# Control_Board1.net
KiCad netlist of a schematic drawn in EAGLE
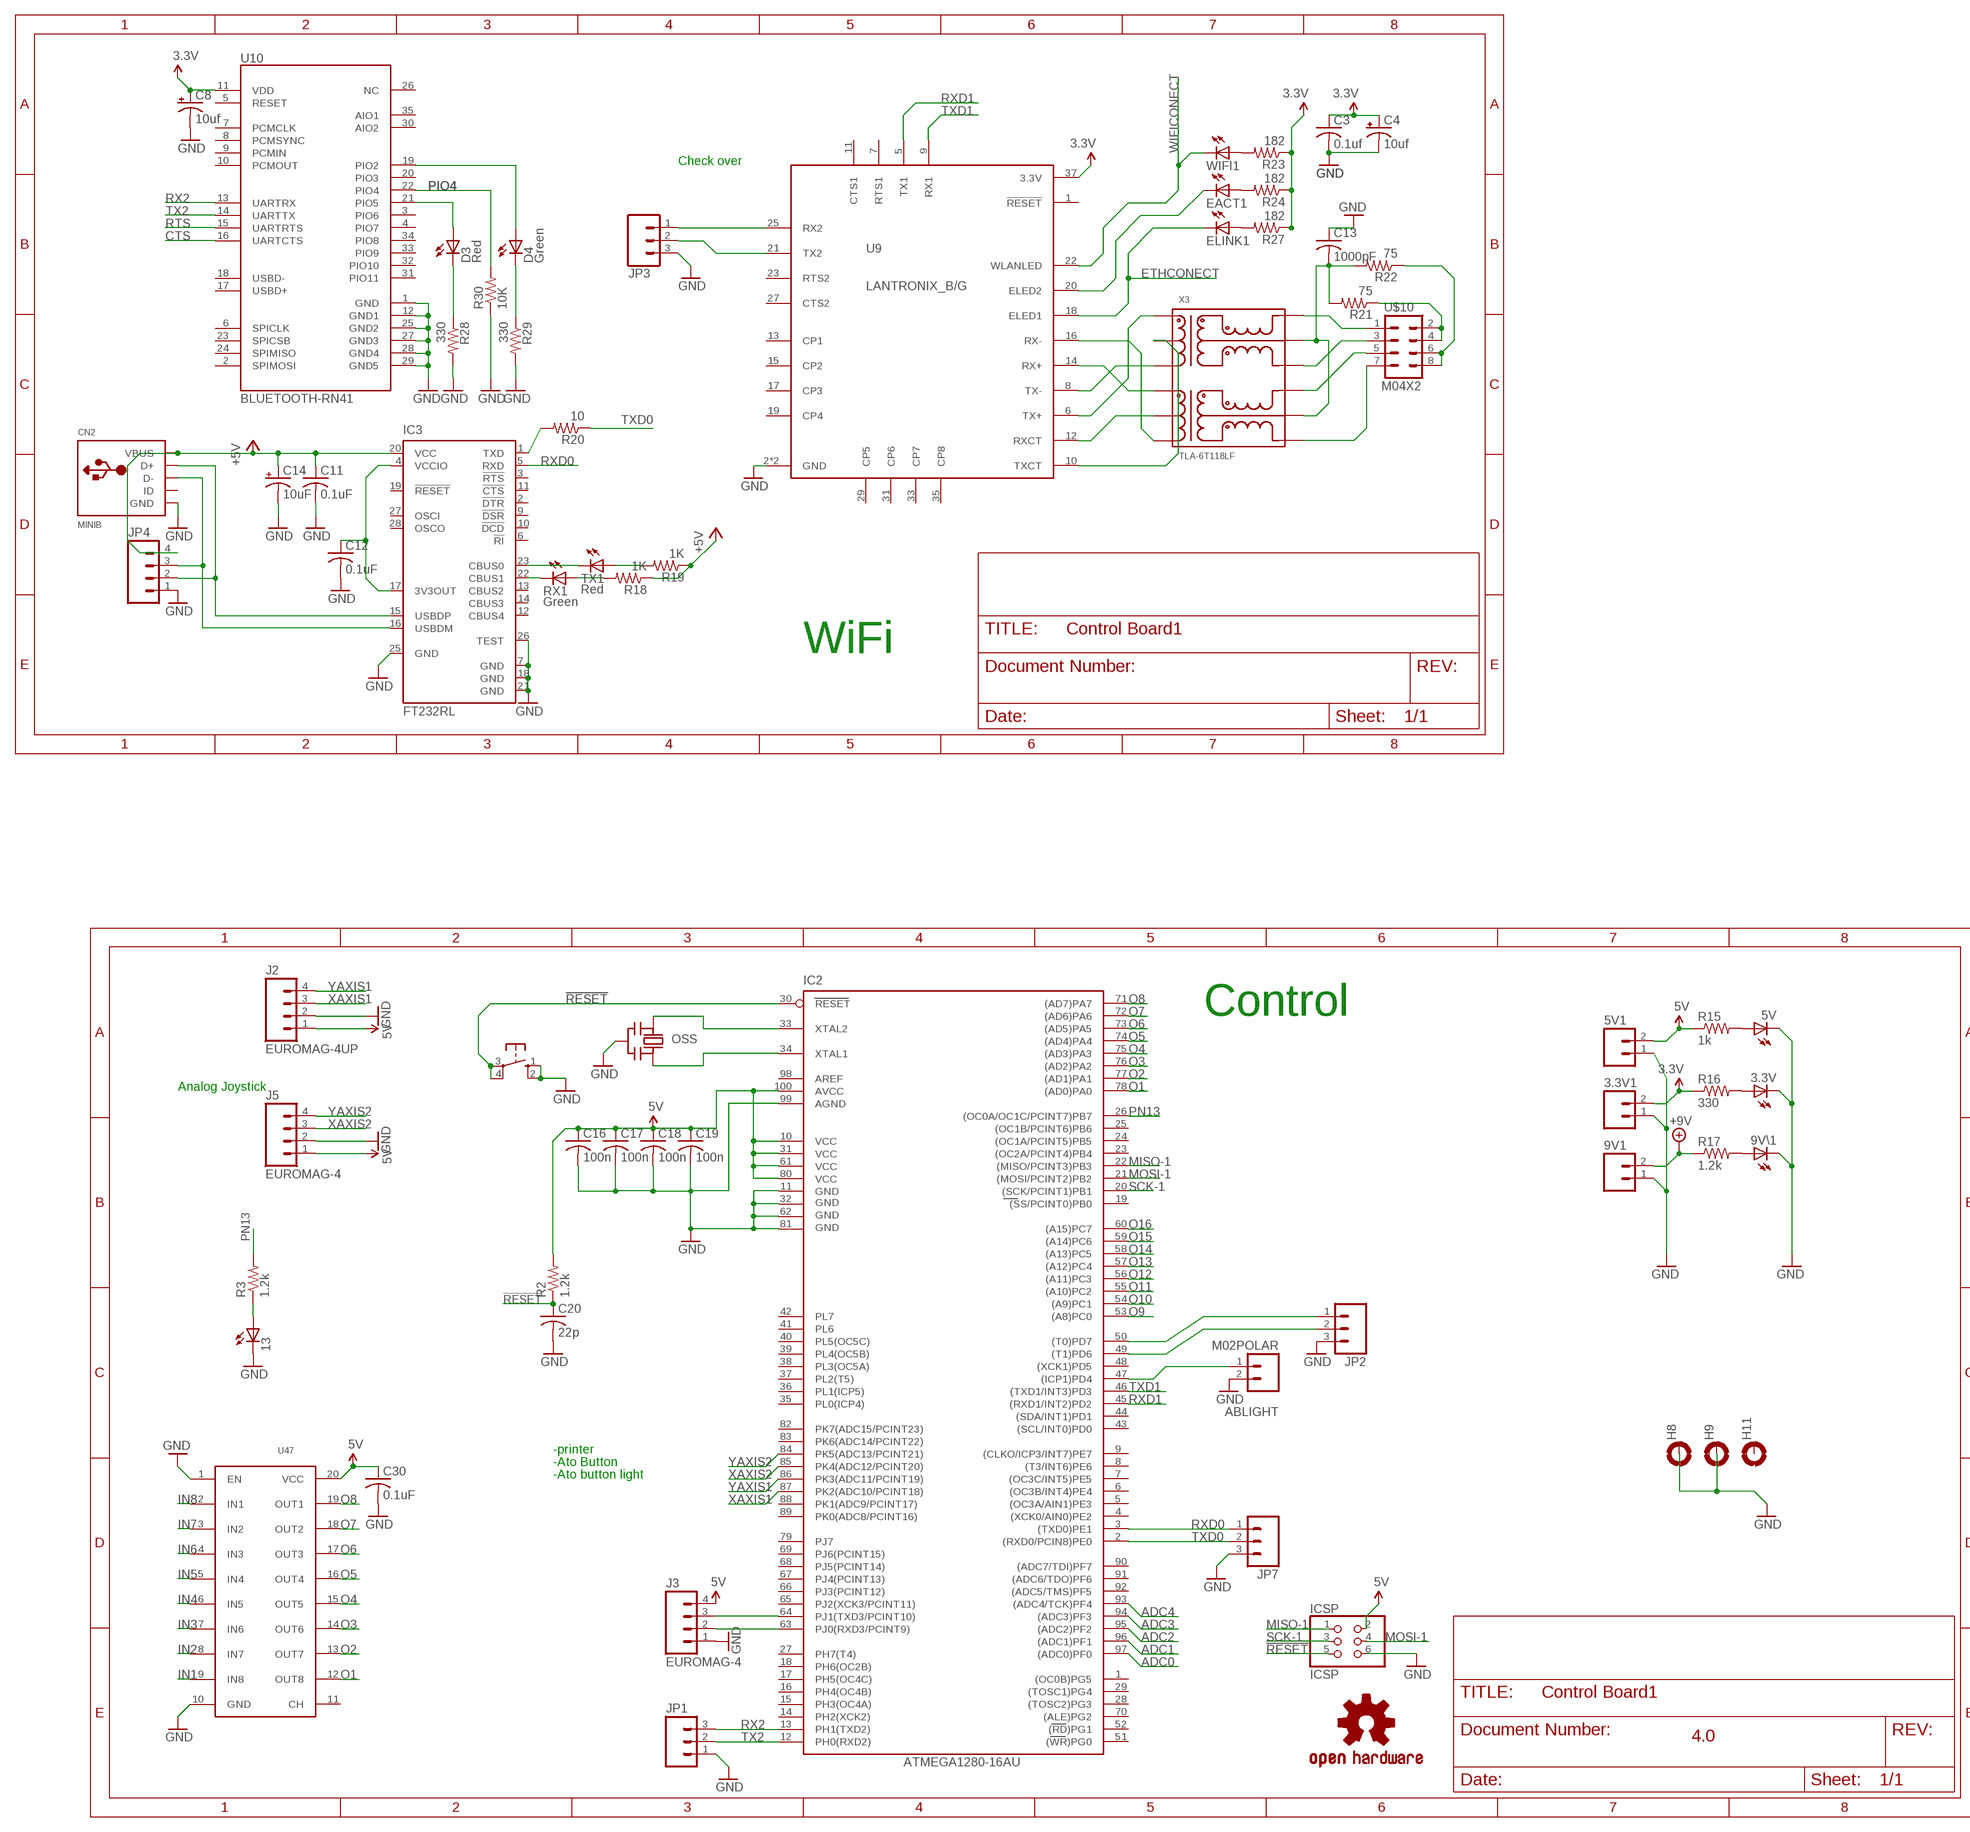
[diagram p0: schematic, sheet 1, part 1 of 2]
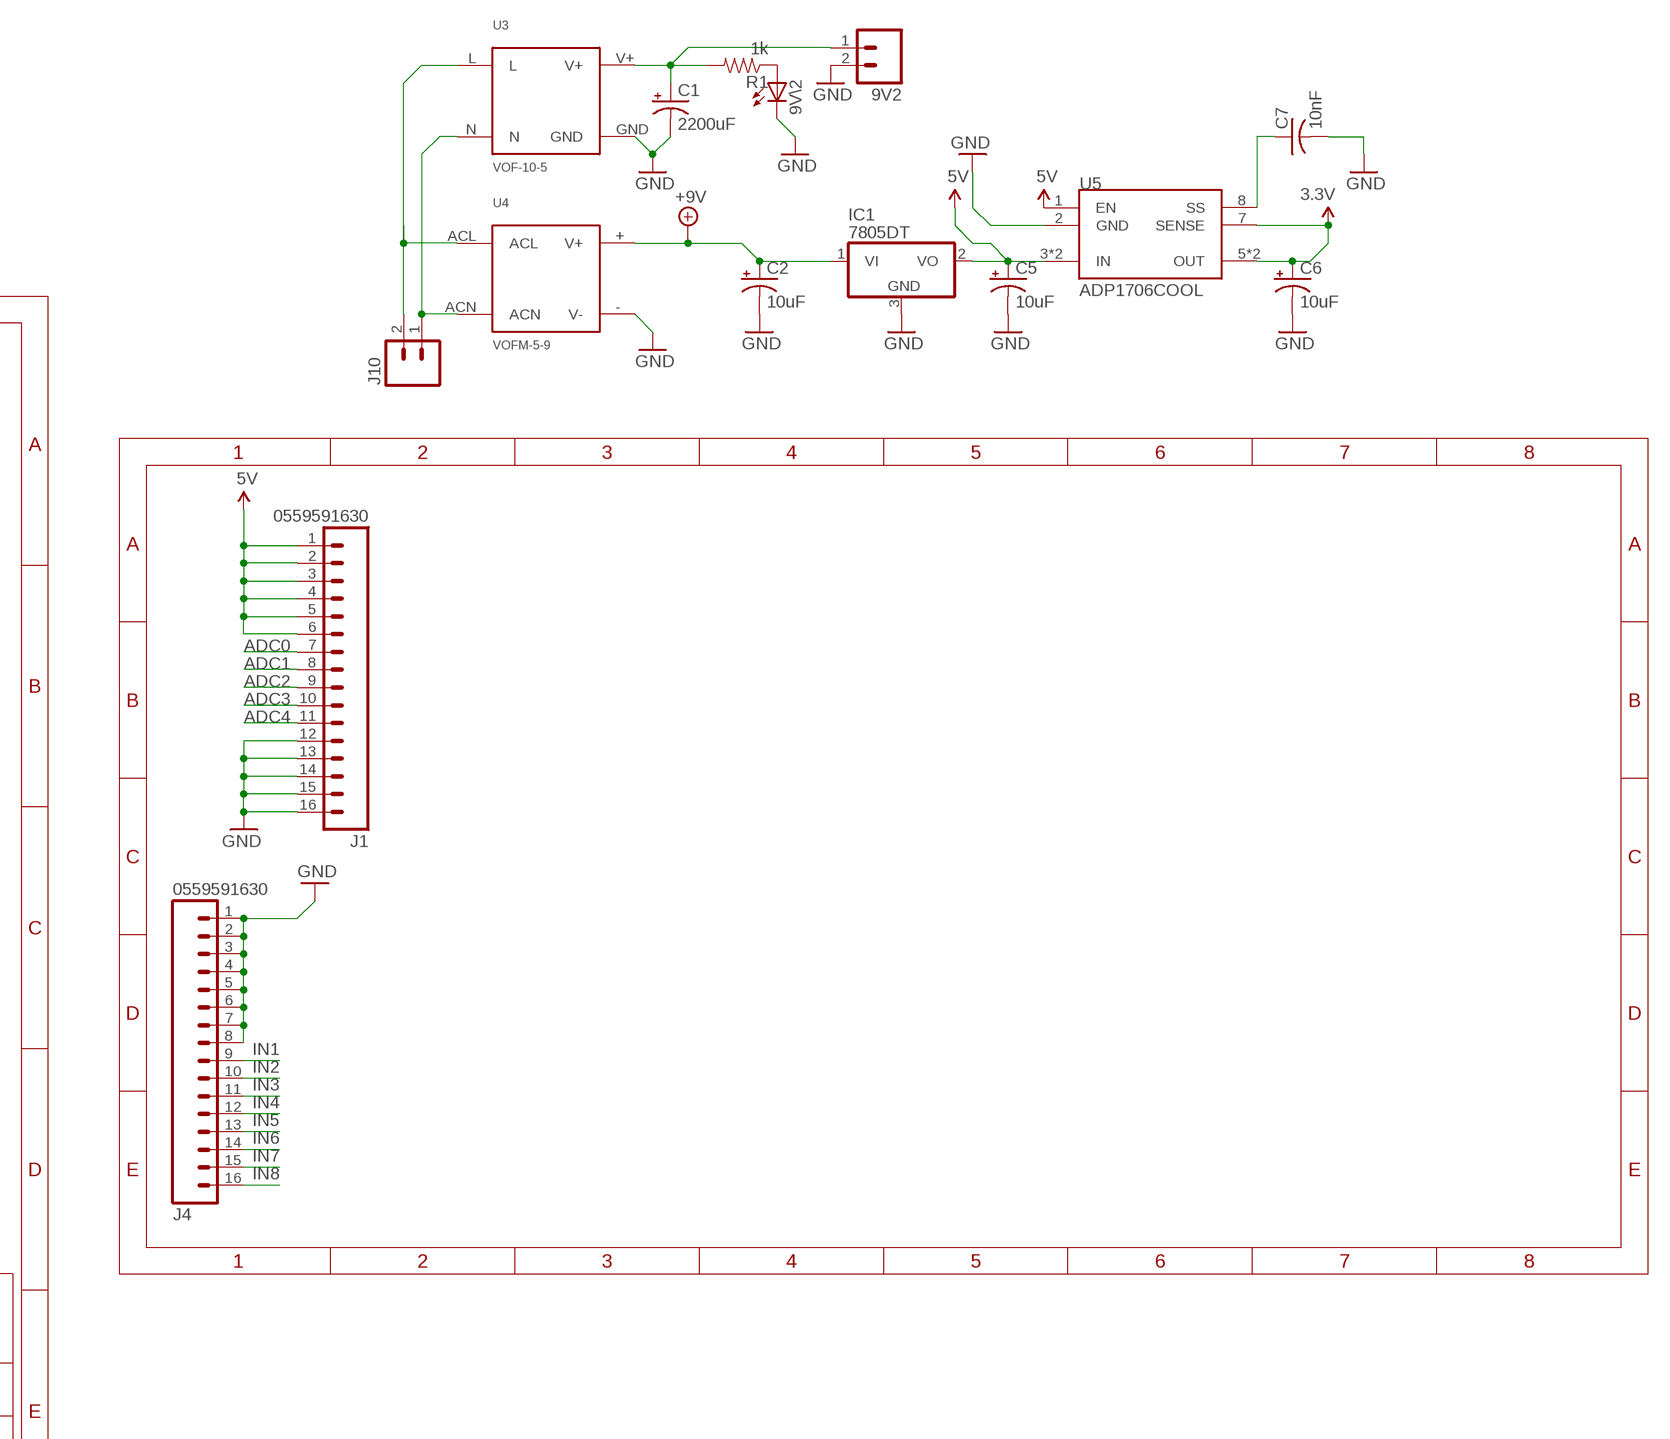
[diagram p1: schematic, sheet 1, part 2 of 2]

(export (version "E")
  (design (tool "Eeschema 10.0.6"))
  (components
    (comp (ref "3.3V")
      (value "LED-FKIT-1206")
      (footprint "eagle-import:FKIT-LED-1206")
      (libsource (lib "eagle-import") (part "LED-FKIT-1206"))
    )
    (comp (ref "3.3V1")
      (value "EUROMAG-290DEG")
      (footprint "eagle-import:M2")
      (libsource (lib "eagle-import") (part "EUROMAG-290DEG"))
    )
    (comp (ref "5V")
      (value "LED-FKIT-1206")
      (footprint "eagle-import:FKIT-LED-1206")
      (libsource (lib "eagle-import") (part "LED-FKIT-1206"))
    )
    (comp (ref "5V1")
      (value "EUROMAG-290DEG")
      (footprint "eagle-import:M2")
      (libsource (lib "eagle-import") (part "EUROMAG-290DEG"))
    )
    (comp (ref "9V1")
      (value "EUROMAG-290DEG")
      (footprint "eagle-import:M2")
      (libsource (lib "eagle-import") (part "EUROMAG-290DEG"))
    )
    (comp (ref "9V2")
      (value "EUROMAG-290DEG")
      (footprint "eagle-import:M2")
      (libsource (lib "eagle-import") (part "EUROMAG-290DEG"))
    )
    (comp (ref "9V\\1")
      (value "LED-FKIT-1206")
      (footprint "eagle-import:FKIT-LED-1206")
      (libsource (lib "eagle-import") (part "LED-FKIT-1206"))
    )
    (comp (ref "9V\\2")
      (value "LED-FKIT-1206")
      (footprint "eagle-import:FKIT-LED-1206")
      (libsource (lib "eagle-import") (part "LED-FKIT-1206"))
    )
    (comp (ref "13")
      (value "LEDCHIP-LED0805")
      (footprint "eagle-import:CHIP-LED0805")
      (libsource (lib "eagle-import") (part "LEDCHIP-LED0805"))
    )
    (comp (ref "ABLIGHT")
      (value "M02POLAR")
      (footprint "eagle-import:MOLEX-1X2")
      (libsource (lib "eagle-import") (part "M02POLAR"))
    )
    (comp (ref "C1")
      (value "2200uF")
      (footprint "eagle-import:EB20D")
      (libsource (lib "eagle-import") (part "CPOL-USE10-20"))
    )
    (comp (ref "C2")
      (value "10uF")
      (footprint "eagle-import:CT3528")
      (libsource (lib "eagle-import") (part "CPOL-USCT3528"))
    )
    (comp (ref "C3")
      (value "0.1uf")
      (footprint "eagle-import:C0805K")
      (libsource (lib "eagle-import") (part "C-USC0805K"))
    )
    (comp (ref "C4")
      (value "10uf")
      (footprint "eagle-import:EIA3528")
      (libsource (lib "eagle-import") (part "CAP_POL3528"))
    )
    (comp (ref "C5")
      (value "10uF")
      (footprint "eagle-import:CT3528")
      (libsource (lib "eagle-import") (part "CPOL-USCT3528"))
    )
    (comp (ref "C6")
      (value "10uF")
      (footprint "eagle-import:CT3528")
      (libsource (lib "eagle-import") (part "CPOL-USCT3528"))
    )
    (comp (ref "C7")
      (value "10nF")
      (footprint "eagle-import:C0805")
      (libsource (lib "eagle-import") (part "C-USC0805"))
    )
    (comp (ref "C8")
      (value "10uf")
      (footprint "eagle-import:EIA3528")
      (libsource (lib "eagle-import") (part "CAP_POL3528"))
    )
    (comp (ref "C11")
      (value "0.1uF")
      (footprint "eagle-import:C0805K")
      (libsource (lib "eagle-import") (part "C-USC0805K"))
    )
    (comp (ref "C12")
      (value "0.1uF")
      (footprint "eagle-import:C0805K")
      (libsource (lib "eagle-import") (part "C-USC0805K"))
    )
    (comp (ref "C13")
      (value "1000pF")
      (footprint "eagle-import:C1812")
      (libsource (lib "eagle-import") (part "C-USC1812"))
    )
    (comp (ref "C14")
      (value "10uF")
      (footprint "eagle-import:EIA3528-KIT")
      (libsource (lib "eagle-import") (part "CAP_POL3528-KIT"))
    )
    (comp (ref "C16")
      (value "100n")
      (footprint "eagle-import:C0805")
      (libsource (lib "eagle-import") (part "C-USC0805"))
    )
    (comp (ref "C17")
      (value "100n")
      (footprint "eagle-import:C0805")
      (libsource (lib "eagle-import") (part "C-USC0805"))
    )
    (comp (ref "C18")
      (value "100n")
      (footprint "eagle-import:C0805")
      (libsource (lib "eagle-import") (part "C-USC0805"))
    )
    (comp (ref "C19")
      (value "100n")
      (footprint "eagle-import:C0805")
      (libsource (lib "eagle-import") (part "C-USC0805"))
    )
    (comp (ref "C20")
      (value "22p")
      (footprint "eagle-import:C0805")
      (libsource (lib "eagle-import") (part "C-USC0805"))
    )
    (comp (ref "C30")
      (value "0.1uF")
      (footprint "eagle-import:C0805")
      (libsource (lib "eagle-import") (part "C-USC0805"))
    )
    (comp (ref "CN2")
      (value "MINIB")
      (footprint "eagle-import:USB-MINIB")
      (libsource (lib "eagle-import") (part "USBMINIB"))
    )
    (comp (ref "D3")
      (value "Red")
      (footprint "eagle-import:CHIP-LED0805")
      (libsource (lib "eagle-import") (part "LEDCHIP-LED0805"))
    )
    (comp (ref "D4")
      (value "Green")
      (footprint "eagle-import:CHIP-LED0805")
      (libsource (lib "eagle-import") (part "LEDCHIP-LED0805"))
    )
    (comp (ref "EACT1")
      (value "LEDCHIP-LED0805")
      (footprint "eagle-import:CHIP-LED0805")
      (libsource (lib "eagle-import") (part "LEDCHIP-LED0805"))
    )
    (comp (ref "ELINK1")
      (value "LEDCHIP-LED0805")
      (footprint "eagle-import:CHIP-LED0805")
      (libsource (lib "eagle-import") (part "LEDCHIP-LED0805"))
    )
    (comp (ref "H8")
      (value "MOUNT-PAD-ROUND2.8")
      (footprint "eagle-import:2,8-PAD")
      (libsource (lib "eagle-import") (part "MOUNT-PAD-ROUND2.8"))
    )
    (comp (ref "H9")
      (value "MOUNT-PAD-ROUND2.8")
      (footprint "eagle-import:2,8-PAD")
      (libsource (lib "eagle-import") (part "MOUNT-PAD-ROUND2.8"))
    )
    (comp (ref "H11")
      (value "MOUNT-PAD-ROUND2.8")
      (footprint "eagle-import:2,8-PAD")
      (libsource (lib "eagle-import") (part "MOUNT-PAD-ROUND2.8"))
    )
    (comp (ref "IC1")
      (value "7805DT")
      (footprint "eagle-import:TO252")
      (libsource (lib "eagle-import") (part "78DT05"))
    )
    (comp (ref "IC2")
      (value "ATMEGA1280-16AU")
      (footprint "eagle-import:TQFP100")
      (libsource (lib "eagle-import") (part "ATMEGAAU1280-16"))
    )
    (comp (ref "IC3")
      (value "FT232RL")
      (footprint "eagle-import:SSOP28")
      (libsource (lib "eagle-import") (part "FT232RL"))
    )
    (comp (ref "ICSP")
      (value "ICSP")
      (footprint "eagle-import:2X03")
      (libsource (lib "eagle-import") (part "PINHD-2X3"))
    )
    (comp (ref "J1")
      (value "0559591630")
      (footprint "eagle-import:0559591630")
      (libsource (lib "eagle-import") (part "0559591630"))
    )
    (comp (ref "J2")
      (value "EUROMAG-4UP")
      (footprint "eagle-import:M4-90")
      (libsource (lib "eagle-import") (part "EUROMAG-4UP"))
    )
    (comp (ref "J3")
      (value "EUROMAG-4")
      (footprint "eagle-import:M4")
      (libsource (lib "eagle-import") (part "EUROMAG-4"))
    )
    (comp (ref "J4")
      (value "0559591630")
      (footprint "eagle-import:0559591630")
      (libsource (lib "eagle-import") (part "0559591630"))
    )
    (comp (ref "J5")
      (value "EUROMAG-4")
      (footprint "eagle-import:M4")
      (libsource (lib "eagle-import") (part "EUROMAG-4"))
    )
    (comp (ref "J10")
      (value "EUROMAG-290DEG")
      (footprint "eagle-import:M2")
      (libsource (lib "eagle-import") (part "EUROMAG-290DEG"))
    )
    (comp (ref "JP1")
      (value "M03POLAR")
      (footprint "eagle-import:MOLEX-1X3")
      (libsource (lib "eagle-import") (part "M03POLAR"))
    )
    (comp (ref "JP2")
      (value "M03POLAR")
      (footprint "eagle-import:MOLEX-1X3")
      (libsource (lib "eagle-import") (part "M03POLAR"))
    )
    (comp (ref "JP3")
      (value "M03POLAR")
      (footprint "eagle-import:MOLEX-1X3")
      (libsource (lib "eagle-import") (part "M03POLAR"))
    )
    (comp (ref "JP4")
      (value "M04LOCK")
      (footprint "eagle-import:1X04_LOCK")
      (libsource (lib "eagle-import") (part "M04LOCK"))
    )
    (comp (ref "JP7")
      (value "M03LOCK")
      (footprint "eagle-import:1X03_LOCK")
      (libsource (lib "eagle-import") (part "M03LOCK"))
    )
    (comp (ref "OSS")
      (value "CERMOSCILL-AWCSR")
      (footprint "eagle-import:AWCSR")
      (libsource (lib "eagle-import") (part "CERMOSCILL-AWCSR"))
    )
    (comp (ref "R1")
      (value "1k")
      (footprint "eagle-import:0805")
      (libsource (lib "eagle-import") (part "RESISTOR0805-RES"))
    )
    (comp (ref "R2")
      (value "1.2k")
      (footprint "eagle-import:0805")
      (libsource (lib "eagle-import") (part "RESISTOR0805-RES"))
    )
    (comp (ref "R3")
      (value "1.2k")
      (footprint "eagle-import:0805")
      (libsource (lib "eagle-import") (part "RESISTOR0805-RES"))
    )
    (comp (ref "R15")
      (value "1k")
      (footprint "eagle-import:0805")
      (libsource (lib "eagle-import") (part "RESISTOR0805-RES"))
    )
    (comp (ref "R16")
      (value "330")
      (footprint "eagle-import:0805")
      (libsource (lib "eagle-import") (part "RESISTOR0805-RES"))
    )
    (comp (ref "R17")
      (value "1.2k")
      (footprint "eagle-import:0805")
      (libsource (lib "eagle-import") (part "RESISTOR0805-RES"))
    )
    (comp (ref "R18")
      (value "1K")
      (footprint "eagle-import:R0805@1")
      (libsource (lib "eagle-import") (part "R-US_R0805"))
    )
    (comp (ref "R19")
      (value "1K")
      (footprint "eagle-import:R0805@1")
      (libsource (lib "eagle-import") (part "R-US_R0805"))
    )
    (comp (ref "R20")
      (value "10")
      (footprint "eagle-import:R0805@1")
      (libsource (lib "eagle-import") (part "R-US_R0805"))
    )
    (comp (ref "R21")
      (value "75")
      (footprint "eagle-import:R0805@1")
      (libsource (lib "eagle-import") (part "R-US_R0805"))
    )
    (comp (ref "R22")
      (value "75")
      (footprint "eagle-import:R0805@1")
      (libsource (lib "eagle-import") (part "R-US_R0805"))
    )
    (comp (ref "R23")
      (value "182")
      (footprint "eagle-import:R0805@1")
      (libsource (lib "eagle-import") (part "R-US_R0805"))
    )
    (comp (ref "R24")
      (value "182")
      (footprint "eagle-import:R0805@1")
      (libsource (lib "eagle-import") (part "R-US_R0805"))
    )
    (comp (ref "R27")
      (value "182")
      (footprint "eagle-import:R0805@1")
      (libsource (lib "eagle-import") (part "R-US_R0805"))
    )
    (comp (ref "R28")
      (value "330")
      (footprint "eagle-import:0805")
      (libsource (lib "eagle-import") (part "RESISTOR0805-RES"))
    )
    (comp (ref "R29")
      (value "330")
      (footprint "eagle-import:0805")
      (libsource (lib "eagle-import") (part "RESISTOR0805-RES"))
    )
    (comp (ref "R30")
      (value "10K")
      (footprint "eagle-import:0805")
      (libsource (lib "eagle-import") (part "RESISTOR0805-RES"))
    )
    (comp (ref "RX1")
      (value "Green")
      (footprint "eagle-import:CHIP-LED0805")
      (libsource (lib "eagle-import") (part "LEDCHIP-LED0805"))
    )
    (comp (ref "S1")
      (value "10-XX")
      (footprint "eagle-import:B3F-10XX")
      (libsource (lib "eagle-import") (part "10-XX"))
    )
    (comp (ref "TX1")
      (value "Red")
      (footprint "eagle-import:CHIP-LED0805")
      (libsource (lib "eagle-import") (part "LEDCHIP-LED0805"))
    )
    (comp (ref "U$3")
      (value "OSHW-LOGOL")
      (footprint "eagle-import:OSHW-LOGO-L")
      (libsource (lib "eagle-import") (part "OSHW-LOGOL"))
    )
    (comp (ref "U$10")
      (value "M04X2")
      (footprint "eagle-import:2X4")
      (libsource (lib "eagle-import") (part "M04X2"))
    )
    (comp (ref "U3")
      (value "VOF-10-5")
      (footprint "eagle-import:VOF-10")
      (libsource (lib "eagle-import") (part "VOF-10"))
    )
    (comp (ref "U4")
      (value "VOFM-5-9")
      (footprint "eagle-import:VOFM-5")
      (libsource (lib "eagle-import") (part "VOFM-5"))
    )
    (comp (ref "U5")
      (value "ADP1706COOL")
      (footprint "eagle-import:SO-8COOL")
      (libsource (lib "eagle-import") (part "ADP1706COOL"))
    )
    (comp (ref "U9")
      (value "LANTRONIX_B/G")
      (footprint "eagle-import:LANA_BTH")
      (libsource (lib "eagle-import") (part "LANTRONIX_A/B"))
    )
    (comp (ref "U10")
      (value "BLUETOOTH-RN41")
      (footprint "eagle-import:RN41")
      (libsource (lib "eagle-import") (part "BLUETOOTH-RN41{dblquote}"))
    )
    (comp (ref "U47")
      (value "MAX6818")
      (footprint "eagle-import:SSOP-20")
      (libsource (lib "eagle-import") (part "MAX6818"))
    )
    (comp (ref "WIFI1")
      (value "LEDCHIP-LED0805")
      (footprint "eagle-import:CHIP-LED0805")
      (libsource (lib "eagle-import") (part "LEDCHIP-LED0805"))
    )
    (comp (ref "X3")
      (value "TLA-6T118LF")
      (footprint "eagle-import:SO-16MOD")
      (libsource (lib "eagle-import") (part "TLA-6T118LF"))
    )
  )
  (nets
    (net (code "1") (name "+5V") (class "Default")
      (node (ref "C11") (pin "1") (pinfunction "1_1") (pintype "passive"))
      (node (ref "C14") (pin "A") (pinfunction "+_A") (pintype "passive"))
      (node (ref "CN2") (pin "VBUS") (pinfunction "VBUS_VBUS") (pintype "power_in"))
      (node (ref "IC3") (pin "20") (pinfunction "VCC_20") (pintype "input"))
      (node (ref "JP4") (pin "4") (pinfunction "4_4") (pintype "passive"))
      (node (ref "R18") (pin "1") (pinfunction "1_1") (pintype "passive"))
      (node (ref "R19") (pin "1") (pinfunction "1_1") (pintype "passive"))
    )
    (net (code "2") (name "+9V") (class "Default")
      (node (ref "9V1") (pin "2") (pinfunction "2_2") (pintype "passive"))
      (node (ref "C2") (pin "+") (pinfunction "+_+") (pintype "passive"))
      (node (ref "IC1") (pin "1") (pinfunction "VI_1") (pintype "input"))
      (node (ref "R17") (pin "1") (pinfunction "1_1") (pintype "passive"))
      (node (ref "U4") (pin "+") (pinfunction "V+_+") (pintype "bidirectional"))
    )
    (net (code "3") (name "/ADC0") (class "Default")
      (node (ref "IC2") (pin "97") (pinfunction "(ADC0)PF0_97") (pintype "bidirectional"))
      (node (ref "J1") (pin "7") (pinfunction "7_7") (pintype "passive"))
    )
    (net (code "4") (name "/ADC1") (class "Default")
      (node (ref "IC2") (pin "96") (pinfunction "(ADC1)PF1_96") (pintype "bidirectional"))
      (node (ref "J1") (pin "8") (pinfunction "8_8") (pintype "passive"))
    )
    (net (code "5") (name "/ADC2") (class "Default")
      (node (ref "IC2") (pin "95") (pinfunction "(ADC2)PF2_95") (pintype "bidirectional"))
      (node (ref "J1") (pin "9") (pinfunction "9_9") (pintype "passive"))
    )
    (net (code "6") (name "/ADC3") (class "Default")
      (node (ref "IC2") (pin "94") (pinfunction "(ADC3)PF3_94") (pintype "bidirectional"))
      (node (ref "J1") (pin "10") (pinfunction "10_10") (pintype "passive"))
    )
    (net (code "7") (name "/ADC4") (class "Default")
      (node (ref "IC2") (pin "93") (pinfunction "(ADC4/TCK)PF4_93") (pintype "bidirectional"))
      (node (ref "J1") (pin "11") (pinfunction "11_11") (pintype "passive"))
    )
    (net (code "8") (name "/CTS") (class "Default")
      (node (ref "U10") (pin "16") (pinfunction "UARTCTS_16") (pintype "bidirectional"))
    )
    (net (code "9") (name "/ETHCONECT") (class "Default")
      (node (ref "ELINK1") (pin "C") (pinfunction "C_C") (pintype "passive"))
      (node (ref "U9") (pin "18") (pinfunction "ELED1_18") (pintype "bidirectional"))
    )
    (net (code "10") (name "/IN1") (class "Default")
      (node (ref "J4") (pin "9") (pinfunction "9_9") (pintype "passive"))
      (node (ref "U47") (pin "9") (pinfunction "IN8_9") (pintype "bidirectional"))
    )
    (net (code "11") (name "/IN2") (class "Default")
      (node (ref "J4") (pin "10") (pinfunction "10_10") (pintype "passive"))
      (node (ref "U47") (pin "8") (pinfunction "IN7_8") (pintype "bidirectional"))
    )
    (net (code "12") (name "/IN3") (class "Default")
      (node (ref "J4") (pin "11") (pinfunction "11_11") (pintype "passive"))
      (node (ref "U47") (pin "7") (pinfunction "IN6_7") (pintype "bidirectional"))
    )
    (net (code "13") (name "/IN4") (class "Default")
      (node (ref "J4") (pin "12") (pinfunction "12_12") (pintype "passive"))
      (node (ref "U47") (pin "6") (pinfunction "IN5_6") (pintype "bidirectional"))
    )
    (net (code "14") (name "/IN5") (class "Default")
      (node (ref "J4") (pin "13") (pinfunction "13_13") (pintype "passive"))
      (node (ref "U47") (pin "5") (pinfunction "IN4_5") (pintype "bidirectional"))
    )
    (net (code "15") (name "/IN6") (class "Default")
      (node (ref "J4") (pin "14") (pinfunction "14_14") (pintype "passive"))
      (node (ref "U47") (pin "4") (pinfunction "IN3_4") (pintype "bidirectional"))
    )
    (net (code "16") (name "/IN7") (class "Default")
      (node (ref "J4") (pin "15") (pinfunction "15_15") (pintype "passive"))
      (node (ref "U47") (pin "3") (pinfunction "IN2_3") (pintype "bidirectional"))
    )
    (net (code "17") (name "/IN8") (class "Default")
      (node (ref "J4") (pin "16") (pinfunction "16_16") (pintype "passive"))
      (node (ref "U47") (pin "2") (pinfunction "IN1_2") (pintype "bidirectional"))
    )
    (net (code "18") (name "/MISO-1") (class "Default")
      (node (ref "IC2") (pin "22") (pinfunction "(MISO/PCINT3)PB3_22") (pintype "bidirectional"))
      (node (ref "ICSP") (pin "1") (pinfunction "1_1") (pintype "passive"))
    )
    (net (code "19") (name "/MOSI-1") (class "Default")
      (node (ref "IC2") (pin "21") (pinfunction "(MOSI/PCINT2)PB2_21") (pintype "bidirectional"))
      (node (ref "ICSP") (pin "4") (pinfunction "4_4") (pintype "passive"))
    )
    (net (code "20") (name "/O1") (class "Default")
      (node (ref "IC2") (pin "78") (pinfunction "(AD0)PA0_78") (pintype "bidirectional"))
      (node (ref "U47") (pin "12") (pinfunction "OUT8_12") (pintype "bidirectional"))
    )
    (net (code "21") (name "/O2") (class "Default")
      (node (ref "IC2") (pin "77") (pinfunction "(AD1)PA1_77") (pintype "bidirectional"))
      (node (ref "U47") (pin "13") (pinfunction "OUT7_13") (pintype "bidirectional"))
    )
    (net (code "22") (name "/O3") (class "Default")
      (node (ref "IC2") (pin "76") (pinfunction "(AD2)PA2_76") (pintype "bidirectional"))
      (node (ref "U47") (pin "14") (pinfunction "OUT6_14") (pintype "bidirectional"))
    )
    (net (code "23") (name "/O4") (class "Default")
      (node (ref "IC2") (pin "75") (pinfunction "(AD3)PA3_75") (pintype "bidirectional"))
      (node (ref "U47") (pin "15") (pinfunction "OUT5_15") (pintype "bidirectional"))
    )
    (net (code "24") (name "/O5") (class "Default")
      (node (ref "IC2") (pin "74") (pinfunction "(AD4)PA4_74") (pintype "bidirectional"))
      (node (ref "U47") (pin "16") (pinfunction "OUT4_16") (pintype "bidirectional"))
    )
    (net (code "25") (name "/O6") (class "Default")
      (node (ref "IC2") (pin "73") (pinfunction "(AD5)PA5_73") (pintype "bidirectional"))
      (node (ref "U47") (pin "17") (pinfunction "OUT3_17") (pintype "bidirectional"))
    )
    (net (code "26") (name "/O7") (class "Default")
      (node (ref "IC2") (pin "72") (pinfunction "(AD6)PA6_72") (pintype "bidirectional"))
      (node (ref "U47") (pin "18") (pinfunction "OUT2_18") (pintype "bidirectional"))
    )
    (net (code "27") (name "/O8") (class "Default")
      (node (ref "IC2") (pin "71") (pinfunction "(AD7)PA7_71") (pintype "bidirectional"))
      (node (ref "U47") (pin "19") (pinfunction "OUT1_19") (pintype "bidirectional"))
    )
    (net (code "28") (name "/O9") (class "Default")
      (node (ref "IC2") (pin "53") (pinfunction "(A8)PC0_53") (pintype "bidirectional"))
    )
    (net (code "29") (name "/O10") (class "Default")
      (node (ref "IC2") (pin "54") (pinfunction "(A9)PC1_54") (pintype "bidirectional"))
    )
    (net (code "30") (name "/O11") (class "Default")
      (node (ref "IC2") (pin "55") (pinfunction "(A10)PC2_55") (pintype "bidirectional"))
    )
    (net (code "31") (name "/O12") (class "Default")
      (node (ref "IC2") (pin "56") (pinfunction "(A11)PC3_56") (pintype "bidirectional"))
    )
    (net (code "32") (name "/O13") (class "Default")
      (node (ref "IC2") (pin "57") (pinfunction "(A12)PC4_57") (pintype "bidirectional"))
    )
    (net (code "33") (name "/O14") (class "Default")
      (node (ref "IC2") (pin "58") (pinfunction "(A13)PC5_58") (pintype "bidirectional"))
    )
    (net (code "34") (name "/O15") (class "Default")
      (node (ref "IC2") (pin "59") (pinfunction "(A14)PC6_59") (pintype "bidirectional"))
    )
    (net (code "35") (name "/O16") (class "Default")
      (node (ref "IC2") (pin "60") (pinfunction "(A15)PC7_60") (pintype "bidirectional"))
    )
    (net (code "36") (name "/PIO4") (class "Default")
      (node (ref "R30") (pin "2") (pinfunction "2_2") (pintype "passive"))
      (node (ref "U10") (pin "22") (pinfunction "PIO4_22") (pintype "bidirectional"))
    )
    (net (code "37") (name "/PN13") (class "Default")
      (node (ref "IC2") (pin "26") (pinfunction "(OC0A/OC1C/PCINT7)PB7_26") (pintype "bidirectional"))
      (node (ref "R3") (pin "2") (pinfunction "2_2") (pintype "passive"))
    )
    (net (code "38") (name "/RTS") (class "Default")
      (node (ref "U10") (pin "15") (pinfunction "UARTRTS_15") (pintype "bidirectional"))
    )
    (net (code "39") (name "/RX2") (class "Default")
      (node (ref "IC2") (pin "13") (pinfunction "PH1(TXD2)_13") (pintype "bidirectional"))
      (node (ref "JP1") (pin "3") (pinfunction "3_3") (pintype "passive"))
      (node (ref "U10") (pin "13") (pinfunction "UARTRX_13") (pintype "bidirectional"))
    )
    (net (code "40") (name "/RXD0") (class "Default")
      (node (ref "IC2") (pin "3") (pinfunction "(TXD0)PE1_3") (pintype "bidirectional"))
      (node (ref "IC3") (pin "5") (pinfunction "RXD_5") (pintype "input"))
      (node (ref "JP7") (pin "1") (pinfunction "1_1") (pintype "passive"))
    )
    (net (code "41") (name "/RXD1") (class "Default")
      (node (ref "IC2") (pin "45") (pinfunction "(RXD1/INT2)PD2_45") (pintype "bidirectional"))
      (node (ref "U9") (pin "5") (pinfunction "TX1_5") (pintype "bidirectional"))
    )
    (net (code "42") (name "/SCK-1") (class "Default")
      (node (ref "IC2") (pin "20") (pinfunction "(SCK/PCINT1)PB1_20") (pintype "bidirectional"))
      (node (ref "ICSP") (pin "3") (pinfunction "3_3") (pintype "passive"))
    )
    (net (code "43") (name "/TX2") (class "Default")
      (node (ref "IC2") (pin "12") (pinfunction "PH0(RXD2)_12") (pintype "bidirectional"))
      (node (ref "JP1") (pin "2") (pinfunction "2_2") (pintype "passive"))
      (node (ref "U10") (pin "14") (pinfunction "UARTTX_14") (pintype "bidirectional"))
    )
    (net (code "44") (name "/TXD0") (class "Default")
      (node (ref "IC2") (pin "2") (pinfunction "(RXD0/PCIN8)PE0_2") (pintype "bidirectional"))
      (node (ref "JP7") (pin "2") (pinfunction "2_2") (pintype "passive"))
      (node (ref "R20") (pin "1") (pinfunction "1_1") (pintype "passive"))
    )
    (net (code "45") (name "/TXD1") (class "Default")
      (node (ref "IC2") (pin "46") (pinfunction "(TXD1/INT3)PD3_46") (pintype "bidirectional"))
      (node (ref "U9") (pin "9") (pinfunction "RX1_9") (pintype "bidirectional"))
    )
    (net (code "46") (name "/WIFICONECT") (class "Default")
      (node (ref "U9") (pin "22") (pinfunction "WLANLED_22") (pintype "bidirectional"))
      (node (ref "WIFI1") (pin "C") (pinfunction "C_C") (pintype "passive"))
    )
    (net (code "47") (name "/XAXIS1") (class "Default")
      (node (ref "IC2") (pin "87") (pinfunction "PK2(ADC10/PCINT18)_87") (pintype "bidirectional"))
      (node (ref "J2") (pin "3") (pinfunction "3_3") (pintype "passive"))
    )
    (net (code "48") (name "/XAXIS2") (class "Default")
      (node (ref "IC2") (pin "85") (pinfunction "PK4(ADC12/PCINT20)_85") (pintype "bidirectional"))
      (node (ref "J5") (pin "3") (pinfunction "3_3") (pintype "passive"))
    )
    (net (code "49") (name "/YAXIS1") (class "Default")
      (node (ref "IC2") (pin "86") (pinfunction "PK3(ADC11/PCINT19)_86") (pintype "bidirectional"))
      (node (ref "J2") (pin "4") (pinfunction "4_4") (pintype "passive"))
    )
    (net (code "50") (name "/YAXIS2") (class "Default")
      (node (ref "IC2") (pin "84") (pinfunction "PK5(ADC13/PCINT21)_84") (pintype "bidirectional"))
      (node (ref "J5") (pin "4") (pinfunction "4_4") (pintype "passive"))
    )
    (net (code "51") (name "/~{RESET}") (class "Default")
      (node (ref "C20") (pin "1") (pinfunction "1_1") (pintype "passive"))
      (node (ref "IC2") (pin "30") (pinfunction "RESET_30") (pintype "input"))
      (node (ref "ICSP") (pin "5") (pinfunction "5_5") (pintype "passive"))
      (node (ref "R2") (pin "1") (pinfunction "1_1") (pintype "passive"))
      (node (ref "S1") (pin "3") (pinfunction "P_3") (pintype "passive"))
      (node (ref "S1") (pin "4") (pinfunction "P1_4") (pintype "passive"))
    )
    (net (code "52") (name "3.3V") (class "Default")
      (node (ref "3.3V1") (pin "2") (pinfunction "2_2") (pintype "passive"))
      (node (ref "C3") (pin "1") (pinfunction "1_1") (pintype "passive"))
      (node (ref "C4") (pin "A") (pinfunction "+_A") (pintype "passive"))
      (node (ref "C6") (pin "+") (pinfunction "+_+") (pintype "passive"))
      (node (ref "C8") (pin "A") (pinfunction "+_A") (pintype "passive"))
      (node (ref "R16") (pin "1") (pinfunction "1_1") (pintype "passive"))
      (node (ref "R23") (pin "1") (pinfunction "1_1") (pintype "passive"))
      (node (ref "R24") (pin "1") (pinfunction "1_1") (pintype "passive"))
      (node (ref "R27") (pin "1") (pinfunction "1_1") (pintype "passive"))
      (node (ref "U10") (pin "11") (pinfunction "VDD_11") (pintype "bidirectional"))
      (node (ref "U5") (pin "5") (pinfunction "OUT_5") (pintype "bidirectional"))
      (node (ref "U5") (pin "6") (pinfunction "OUT_6") (pintype "bidirectional"))
      (node (ref "U5") (pin "7") (pinfunction "SENSE_7") (pintype "bidirectional"))
      (node (ref "U9") (pin "37") (pinfunction "3.3V_37") (pintype "bidirectional"))
    )
    (net (code "53") (name "5V") (class "Default")
      (node (ref "5V1") (pin "2") (pinfunction "2_2") (pintype "passive"))
      (node (ref "C16") (pin "1") (pinfunction "1_1") (pintype "passive"))
      (node (ref "C17") (pin "1") (pinfunction "1_1") (pintype "passive"))
      (node (ref "C18") (pin "1") (pinfunction "1_1") (pintype "passive"))
      (node (ref "C19") (pin "1") (pinfunction "1_1") (pintype "passive"))
      (node (ref "C30") (pin "1") (pinfunction "1_1") (pintype "passive"))
      (node (ref "C5") (pin "+") (pinfunction "+_+") (pintype "passive"))
      (node (ref "IC1") (pin "2") (pinfunction "VO_2") (pintype "passive"))
      (node (ref "IC2") (pin "10") (pinfunction "VCC_10") (pintype "power_in"))
      (node (ref "IC2") (pin "100") (pinfunction "AVCC_100") (pintype "power_in"))
      (node (ref "IC2") (pin "31") (pinfunction "VCC1_31") (pintype "power_in"))
      (node (ref "IC2") (pin "61") (pinfunction "VCC2_61") (pintype "power_in"))
      (node (ref "IC2") (pin "80") (pinfunction "VCC3_80") (pintype "power_in"))
      (node (ref "ICSP") (pin "2") (pinfunction "2_2") (pintype "passive"))
      (node (ref "J1") (pin "1") (pinfunction "1_1") (pintype "passive"))
      (node (ref "J1") (pin "2") (pinfunction "2_2") (pintype "passive"))
      (node (ref "J1") (pin "3") (pinfunction "3_3") (pintype "passive"))
      (node (ref "J1") (pin "4") (pinfunction "4_4") (pintype "passive"))
      (node (ref "J1") (pin "5") (pinfunction "5_5") (pintype "passive"))
      (node (ref "J1") (pin "6") (pinfunction "6_6") (pintype "passive"))
      (node (ref "J2") (pin "1") (pinfunction "1_1") (pintype "passive"))
      (node (ref "J3") (pin "4") (pinfunction "4_4") (pintype "passive"))
      (node (ref "J5") (pin "1") (pinfunction "1_1") (pintype "passive"))
      (node (ref "R15") (pin "1") (pinfunction "1_1") (pintype "passive"))
      (node (ref "R2") (pin "2") (pinfunction "2_2") (pintype "passive"))
      (node (ref "U47") (pin "20") (pinfunction "VCC_20") (pintype "bidirectional"))
      (node (ref "U5") (pin "1") (pinfunction "EN_1") (pintype "bidirectional"))
      (node (ref "U5") (pin "3") (pinfunction "IN_3") (pintype "bidirectional"))
      (node (ref "U5") (pin "4") (pinfunction "IN_4") (pintype "bidirectional"))
    )
    (net (code "54") (name "GND") (class "Default")
      (node (ref "13") (pin "C") (pinfunction "C_C") (pintype "passive"))
      (node (ref "3.3V") (pin "C") (pinfunction "C_C") (pintype "passive"))
      (node (ref "3.3V1") (pin "1") (pinfunction "1_1") (pintype "passive"))
      (node (ref "5V") (pin "C") (pinfunction "C_C") (pintype "passive"))
      (node (ref "5V1") (pin "1") (pinfunction "1_1") (pintype "passive"))
      (node (ref "9V1") (pin "1") (pinfunction "1_1") (pintype "passive"))
      (node (ref "9V2") (pin "2") (pinfunction "2_2") (pintype "passive"))
      (node (ref "9V\\1") (pin "C") (pinfunction "C_C") (pintype "passive"))
      (node (ref "9V\\2") (pin "C") (pinfunction "C_C") (pintype "passive"))
      (node (ref "ABLIGHT") (pin "2") (pinfunction "2_2") (pintype "passive"))
      (node (ref "C1") (pin "-") (pinfunction "-_-") (pintype "passive"))
      (node (ref "C11") (pin "2") (pinfunction "2_2") (pintype "passive"))
      (node (ref "C12") (pin "2") (pinfunction "2_2") (pintype "passive"))
      (node (ref "C13") (pin "1") (pinfunction "1_1") (pintype "passive"))
      (node (ref "C14") (pin "C") (pinfunction "-_C") (pintype "passive"))
      (node (ref "C16") (pin "2") (pinfunction "2_2") (pintype "passive"))
      (node (ref "C17") (pin "2") (pinfunction "2_2") (pintype "passive"))
      (node (ref "C18") (pin "2") (pinfunction "2_2") (pintype "passive"))
      (node (ref "C19") (pin "2") (pinfunction "2_2") (pintype "passive"))
      (node (ref "C2") (pin "-") (pinfunction "-_-") (pintype "passive"))
      (node (ref "C20") (pin "2") (pinfunction "2_2") (pintype "passive"))
      (node (ref "C3") (pin "2") (pinfunction "2_2") (pintype "passive"))
      (node (ref "C30") (pin "2") (pinfunction "2_2") (pintype "passive"))
      (node (ref "C4") (pin "C") (pinfunction "-_C") (pintype "passive"))
      (node (ref "C5") (pin "-") (pinfunction "-_-") (pintype "passive"))
      (node (ref "C6") (pin "-") (pinfunction "-_-") (pintype "passive"))
      (node (ref "C7") (pin "2") (pinfunction "2_2") (pintype "passive"))
      (node (ref "C8") (pin "C") (pinfunction "-_C") (pintype "passive"))
      (node (ref "CN2") (pin "GND") (pinfunction "GND_GND") (pintype "power_in"))
      (node (ref "H8") (pin "B2,8") (pinfunction "MOUNT_B2,8") (pintype "passive"))
      (node (ref "H9") (pin "B2,8") (pinfunction "MOUNT_B2,8") (pintype "passive"))
      (node (ref "IC1") (pin "3") (pinfunction "GND_3") (pintype "passive"))
      (node (ref "IC2") (pin "11") (pinfunction "GND_11") (pintype "power_in"))
      (node (ref "IC2") (pin "32") (pinfunction "GND1_32") (pintype "power_in"))
      (node (ref "IC2") (pin "62") (pinfunction "GND2_62") (pintype "power_in"))
      (node (ref "IC2") (pin "81") (pinfunction "GND3_81") (pintype "power_in"))
      (node (ref "IC2") (pin "99") (pinfunction "AGND_99") (pintype "power_in"))
      (node (ref "IC3") (pin "18") (pinfunction "GND_18") (pintype "input"))
      (node (ref "IC3") (pin "21") (pinfunction "GND_21") (pintype "input"))
      (node (ref "IC3") (pin "25") (pinfunction "GND_25") (pintype "input"))
      (node (ref "IC3") (pin "26") (pinfunction "TEST_26") (pintype "input"))
      (node (ref "IC3") (pin "7") (pinfunction "GND_7") (pintype "input"))
      (node (ref "ICSP") (pin "6") (pinfunction "6_6") (pintype "passive"))
      (node (ref "J1") (pin "12") (pinfunction "12_12") (pintype "passive"))
      (node (ref "J1") (pin "13") (pinfunction "13_13") (pintype "passive"))
      (node (ref "J1") (pin "14") (pinfunction "14_14") (pintype "passive"))
      (node (ref "J1") (pin "15") (pinfunction "15_15") (pintype "passive"))
      (node (ref "J1") (pin "16") (pinfunction "16_16") (pintype "passive"))
      (node (ref "J2") (pin "2") (pinfunction "2_2") (pintype "passive"))
      (node (ref "J3") (pin "1") (pinfunction "1_1") (pintype "passive"))
      (node (ref "J4") (pin "1") (pinfunction "1_1") (pintype "passive"))
      (node (ref "J4") (pin "2") (pinfunction "2_2") (pintype "passive"))
      (node (ref "J4") (pin "3") (pinfunction "3_3") (pintype "passive"))
      (node (ref "J4") (pin "4") (pinfunction "4_4") (pintype "passive"))
      (node (ref "J4") (pin "5") (pinfunction "5_5") (pintype "passive"))
      (node (ref "J4") (pin "6") (pinfunction "6_6") (pintype "passive"))
      (node (ref "J4") (pin "7") (pinfunction "7_7") (pintype "passive"))
      (node (ref "J4") (pin "8") (pinfunction "8_8") (pintype "passive"))
      (node (ref "J5") (pin "2") (pinfunction "2_2") (pintype "passive"))
      (node (ref "JP1") (pin "1") (pinfunction "1_1") (pintype "passive"))
      (node (ref "JP2") (pin "3") (pinfunction "3_3") (pintype "passive"))
      (node (ref "JP3") (pin "3") (pinfunction "3_3") (pintype "passive"))
      (node (ref "JP4") (pin "1") (pinfunction "1_1") (pintype "passive"))
      (node (ref "JP7") (pin "3") (pinfunction "3_3") (pintype "passive"))
      (node (ref "OSS") (pin "2") (pinfunction "GND_2") (pintype "bidirectional"))
      (node (ref "R28") (pin "2") (pinfunction "2_2") (pintype "passive"))
      (node (ref "R29") (pin "2") (pinfunction "2_2") (pintype "passive"))
      (node (ref "R30") (pin "1") (pinfunction "1_1") (pintype "passive"))
      (node (ref "S1") (pin "1") (pinfunction "S_1") (pintype "passive"))
      (node (ref "S1") (pin "2") (pinfunction "S1_2") (pintype "passive"))
      (node (ref "U10") (pin "1") (pinfunction "GND_1") (pintype "bidirectional"))
      (node (ref "U10") (pin "12") (pinfunction "GND1_12") (pintype "bidirectional"))
      (node (ref "U10") (pin "25") (pinfunction "GND2_25") (pintype "bidirectional"))
      (node (ref "U10") (pin "27") (pinfunction "GND3_27") (pintype "bidirectional"))
      (node (ref "U10") (pin "28") (pinfunction "GND4_28") (pintype "bidirectional"))
      (node (ref "U10") (pin "29") (pinfunction "GND5_29") (pintype "bidirectional"))
      (node (ref "U3") (pin "GND") (pinfunction "GND_GND") (pintype "bidirectional"))
      (node (ref "U4") (pin "-") (pinfunction "V-_-") (pintype "bidirectional"))
      (node (ref "U47") (pin "1") (pinfunction "EN_1") (pintype "bidirectional"))
      (node (ref "U47") (pin "10") (pinfunction "GND_10") (pintype "bidirectional"))
      (node (ref "U5") (pin "2") (pinfunction "GND_2") (pintype "bidirectional"))
      (node (ref "U9") (pin "2") (pinfunction "GND_2") (pintype "bidirectional"))
      (node (ref "U9") (pin "39") (pinfunction "GND_39") (pintype "bidirectional"))
    )
    (net (code "55") (name "Net-(3.3V-PadA)") (class "Default")
      (node (ref "3.3V") (pin "A") (pinfunction "A_A") (pintype "passive"))
      (node (ref "R16") (pin "2") (pinfunction "2_2") (pintype "passive"))
    )
    (net (code "56") (name "Net-(5V-PadA)") (class "Default")
      (node (ref "5V") (pin "A") (pinfunction "A_A") (pintype "passive"))
      (node (ref "R15") (pin "2") (pinfunction "2_2") (pintype "passive"))
    )
    (net (code "57") (name "Net-(9V2-Pad1)") (class "Default")
      (node (ref "9V2") (pin "1") (pinfunction "1_1") (pintype "passive"))
      (node (ref "C1") (pin "+") (pinfunction "+_+") (pintype "passive"))
      (node (ref "R1") (pin "2") (pinfunction "2_2") (pintype "passive"))
      (node (ref "U3") (pin "V+") (pinfunction "V+_V+") (pintype "bidirectional"))
    )
    (net (code "58") (name "Net-(9V\\1-PadA)") (class "Default")
      (node (ref "9V\\1") (pin "A") (pinfunction "A_A") (pintype "passive"))
      (node (ref "R17") (pin "2") (pinfunction "2_2") (pintype "passive"))
    )
    (net (code "59") (name "Net-(9V\\2-PadA)") (class "Default")
      (node (ref "9V\\2") (pin "A") (pinfunction "A_A") (pintype "passive"))
      (node (ref "R1") (pin "1") (pinfunction "1_1") (pintype "passive"))
    )
    (net (code "60") (name "Net-(13-PadA)") (class "Default")
      (node (ref "13") (pin "A") (pinfunction "A_A") (pintype "passive"))
      (node (ref "R3") (pin "1") (pinfunction "1_1") (pintype "passive"))
    )
    (net (code "61") (name "Net-(C13-Pad2)") (class "Default")
      (node (ref "C13") (pin "2") (pinfunction "2_2") (pintype "passive"))
      (node (ref "R21") (pin "2") (pinfunction "2_2") (pintype "passive"))
      (node (ref "R22") (pin "2") (pinfunction "2_2") (pintype "passive"))
      (node (ref "X3") (pin "10") (pinfunction "10_10") (pintype "bidirectional"))
      (node (ref "X3") (pin "15") (pinfunction "15_15") (pintype "bidirectional"))
    )
    (net (code "62") (name "Net-(D3-PadC)") (class "Default")
      (node (ref "D3") (pin "C") (pinfunction "C_C") (pintype "passive"))
      (node (ref "R28") (pin "1") (pinfunction "1_1") (pintype "passive"))
    )
    (net (code "63") (name "Net-(D4-PadC)") (class "Default")
      (node (ref "D4") (pin "C") (pinfunction "C_C") (pintype "passive"))
      (node (ref "R29") (pin "1") (pinfunction "1_1") (pintype "passive"))
    )
    (net (code "64") (name "Net-(EACT1-PadA)") (class "Default")
      (node (ref "EACT1") (pin "A") (pinfunction "A_A") (pintype "passive"))
      (node (ref "R24") (pin "2") (pinfunction "2_2") (pintype "passive"))
    )
    (net (code "65") (name "Net-(ELINK1-PadA)") (class "Default")
      (node (ref "ELINK1") (pin "A") (pinfunction "A_A") (pintype "passive"))
      (node (ref "R27") (pin "2") (pinfunction "2_2") (pintype "passive"))
    )
    (net (code "66") (name "Net-(IC2-(ICP1)PD4)") (class "Default")
      (node (ref "ABLIGHT") (pin "1") (pinfunction "1_1") (pintype "passive"))
      (node (ref "IC2") (pin "47") (pinfunction "(ICP1)PD4_47") (pintype "bidirectional"))
    )
    (net (code "67") (name "Net-(IC2-(T0)PD7)") (class "Default")
      (node (ref "IC2") (pin "50") (pinfunction "(T0)PD7_50") (pintype "bidirectional"))
      (node (ref "JP2") (pin "1") (pinfunction "1_1") (pintype "passive"))
    )
    (net (code "68") (name "Net-(IC2-(T1)PD6)") (class "Default")
      (node (ref "IC2") (pin "49") (pinfunction "(T1)PD6_49") (pintype "bidirectional"))
      (node (ref "JP2") (pin "2") (pinfunction "2_2") (pintype "passive"))
    )
    (net (code "69") (name "Net-(IC2-PJ0(RXD3{slash}PCINT9))") (class "Default")
      (node (ref "IC2") (pin "63") (pinfunction "PJ0(RXD3/PCINT9)_63") (pintype "bidirectional"))
      (node (ref "J3") (pin "2") (pinfunction "2_2") (pintype "passive"))
    )
    (net (code "70") (name "Net-(IC2-PJ1(TXD3{slash}PCINT10))") (class "Default")
      (node (ref "IC2") (pin "64") (pinfunction "PJ1(TXD3/PCINT10)_64") (pintype "bidirectional"))
      (node (ref "J3") (pin "3") (pinfunction "3_3") (pintype "passive"))
    )
    (net (code "71") (name "Net-(IC2-XTAL1)") (class "Default")
      (node (ref "IC2") (pin "34") (pinfunction "XTAL1_34") (pintype "input"))
      (node (ref "OSS") (pin "3") (pinfunction "OUT_3") (pintype "bidirectional"))
    )
    (net (code "72") (name "Net-(IC2-XTAL2)") (class "Default")
      (node (ref "IC2") (pin "33") (pinfunction "XTAL2_33") (pintype "output"))
      (node (ref "OSS") (pin "1") (pinfunction "IN_1") (pintype "bidirectional"))
    )
    (net (code "73") (name "Net-(IC3-3V3OUT)") (class "Default")
      (node (ref "C12") (pin "1") (pinfunction "1_1") (pintype "passive"))
      (node (ref "IC3") (pin "17") (pinfunction "3V3OUT_17") (pintype "input"))
      (node (ref "IC3") (pin "4") (pinfunction "VCCIO_4") (pintype "input"))
    )
    (net (code "74") (name "Net-(IC3-CBUS0)") (class "Default")
      (node (ref "IC3") (pin "23") (pinfunction "CBUS0_23") (pintype "input"))
      (node (ref "TX1") (pin "C") (pinfunction "C_C") (pintype "passive"))
    )
    (net (code "75") (name "Net-(IC3-CBUS1)") (class "Default")
      (node (ref "IC3") (pin "22") (pinfunction "CBUS1_22") (pintype "input"))
      (node (ref "RX1") (pin "C") (pinfunction "C_C") (pintype "passive"))
    )
    (net (code "76") (name "Net-(IC3-TXD)") (class "Default")
      (node (ref "IC3") (pin "1") (pinfunction "TXD_1") (pintype "input"))
      (node (ref "R20") (pin "2") (pinfunction "2_2") (pintype "passive"))
    )
    (net (code "77") (name "Net-(IC3-USBDM)") (class "Default")
      (node (ref "CN2") (pin "D-") (pinfunction "D-_D-") (pintype "bidirectional"))
      (node (ref "IC3") (pin "16") (pinfunction "USBDM_16") (pintype "input"))
      (node (ref "JP4") (pin "3") (pinfunction "3_3") (pintype "passive"))
    )
    (net (code "78") (name "Net-(IC3-USBDP)") (class "Default")
      (node (ref "CN2") (pin "D+") (pinfunction "D+_D+") (pintype "bidirectional"))
      (node (ref "IC3") (pin "15") (pinfunction "USBDP_15") (pintype "input"))
      (node (ref "JP4") (pin "2") (pinfunction "2_2") (pintype "passive"))
    )
    (net (code "79") (name "Net-(J10-Pad1)") (class "Default")
      (node (ref "J10") (pin "1") (pinfunction "1_1") (pintype "passive"))
      (node (ref "U3") (pin "N") (pinfunction "N_N") (pintype "bidirectional"))
      (node (ref "U4") (pin "ACN") (pinfunction "ACN_ACN") (pintype "bidirectional"))
    )
    (net (code "80") (name "Net-(J10-Pad2)") (class "Default")
      (node (ref "J10") (pin "2") (pinfunction "2_2") (pintype "passive"))
      (node (ref "U3") (pin "L") (pinfunction "L_L") (pintype "bidirectional"))
      (node (ref "U4") (pin "ACL") (pinfunction "ACL_ACL") (pintype "bidirectional"))
    )
    (net (code "81") (name "Net-(R18-Pad2)") (class "Default")
      (node (ref "R18") (pin "2") (pinfunction "2_2") (pintype "passive"))
      (node (ref "RX1") (pin "A") (pinfunction "A_A") (pintype "passive"))
    )
    (net (code "82") (name "Net-(R19-Pad2)") (class "Default")
      (node (ref "R19") (pin "2") (pinfunction "2_2") (pintype "passive"))
      (node (ref "TX1") (pin "A") (pinfunction "A_A") (pintype "passive"))
    )
    (net (code "83") (name "Net-(R21-Pad1)") (class "Default")
      (node (ref "R21") (pin "1") (pinfunction "1_1") (pintype "passive"))
      (node (ref "U$10") (pin "2") (pinfunction "2_2") (pintype "passive"))
      (node (ref "U$10") (pin "4") (pinfunction "4_4") (pintype "passive"))
    )
    (net (code "84") (name "Net-(R22-Pad1)") (class "Default")
      (node (ref "R22") (pin "1") (pinfunction "1_1") (pintype "passive"))
      (node (ref "U$10") (pin "6") (pinfunction "6_6") (pintype "passive"))
      (node (ref "U$10") (pin "8") (pinfunction "8_8") (pintype "passive"))
    )
    (net (code "85") (name "Net-(R23-Pad2)") (class "Default")
      (node (ref "R23") (pin "2") (pinfunction "2_2") (pintype "passive"))
      (node (ref "WIFI1") (pin "A") (pinfunction "A_A") (pintype "passive"))
    )
    (net (code "86") (name "Net-(U$10-Pad1)") (class "Default")
      (node (ref "U$10") (pin "1") (pinfunction "1_1") (pintype "passive"))
      (node (ref "X3") (pin "16") (pinfunction "16_16") (pintype "bidirectional"))
    )
    (net (code "87") (name "Net-(U$10-Pad3)") (class "Default")
      (node (ref "U$10") (pin "3") (pinfunction "3_3") (pintype "passive"))
      (node (ref "X3") (pin "14") (pinfunction "14_14") (pintype "bidirectional"))
    )
    (net (code "88") (name "Net-(U$10-Pad5)") (class "Default")
      (node (ref "U$10") (pin "5") (pinfunction "5_5") (pintype "passive"))
      (node (ref "X3") (pin "11") (pinfunction "11_11") (pintype "bidirectional"))
    )
    (net (code "89") (name "Net-(U$10-Pad7)") (class "Default")
      (node (ref "U$10") (pin "7") (pinfunction "7_7") (pintype "passive"))
      (node (ref "X3") (pin "9") (pinfunction "9_9") (pintype "bidirectional"))
    )
    (net (code "90") (name "Net-(U5-SS)") (class "Default")
      (node (ref "C7") (pin "1") (pinfunction "1_1") (pintype "passive"))
      (node (ref "U5") (pin "8") (pinfunction "SS_8") (pintype "bidirectional"))
    )
    (net (code "91") (name "Net-(U9-ELED2)") (class "Default")
      (node (ref "EACT1") (pin "C") (pinfunction "C_C") (pintype "passive"))
      (node (ref "U9") (pin "20") (pinfunction "ELED2_20") (pintype "bidirectional"))
    )
    (net (code "92") (name "Net-(U9-RX+)") (class "Default")
      (node (ref "U9") (pin "14") (pinfunction "RX+_14") (pintype "bidirectional"))
      (node (ref "X3") (pin "6") (pinfunction "6_6") (pintype "bidirectional"))
    )
    (net (code "93") (name "Net-(U9-RX-)") (class "Default")
      (node (ref "U9") (pin "16") (pinfunction "RX-_16") (pintype "bidirectional"))
      (node (ref "X3") (pin "8") (pinfunction "8_8") (pintype "bidirectional"))
    )
    (net (code "94") (name "Net-(U9-RX2)") (class "Default")
      (node (ref "JP3") (pin "1") (pinfunction "1_1") (pintype "passive"))
      (node (ref "U9") (pin "25") (pinfunction "RX2_25") (pintype "bidirectional"))
    )
    (net (code "95") (name "Net-(U9-RXCT)") (class "Default")
      (node (ref "U9") (pin "12") (pinfunction "RXCT_12") (pintype "bidirectional"))
      (node (ref "X3") (pin "7") (pinfunction "7_7") (pintype "bidirectional"))
    )
    (net (code "96") (name "Net-(U9-TX+)") (class "Default")
      (node (ref "U9") (pin "6") (pinfunction "TX+_6") (pintype "bidirectional"))
      (node (ref "X3") (pin "1") (pinfunction "1_1") (pintype "bidirectional"))
    )
    (net (code "97") (name "Net-(U9-TX-)") (class "Default")
      (node (ref "U9") (pin "8") (pinfunction "TX-_8") (pintype "bidirectional"))
      (node (ref "X3") (pin "3") (pinfunction "3_3") (pintype "bidirectional"))
    )
    (net (code "98") (name "Net-(U9-TX2)") (class "Default")
      (node (ref "JP3") (pin "2") (pinfunction "2_2") (pintype "passive"))
      (node (ref "U9") (pin "21") (pinfunction "TX2_21") (pintype "bidirectional"))
    )
    (net (code "99") (name "Net-(U9-TXCT)") (class "Default")
      (node (ref "U9") (pin "10") (pinfunction "TXCT_10") (pintype "bidirectional"))
      (node (ref "X3") (pin "2") (pinfunction "2_2") (pintype "bidirectional"))
    )
    (net (code "100") (name "Net-(U10-PIO2)") (class "Default")
      (node (ref "D4") (pin "A") (pinfunction "A_A") (pintype "passive"))
      (node (ref "U10") (pin "19") (pinfunction "PIO2_19") (pintype "bidirectional"))
    )
    (net (code "101") (name "Net-(U10-PIO5)") (class "Default")
      (node (ref "D3") (pin "A") (pinfunction "A_A") (pintype "passive"))
      (node (ref "U10") (pin "21") (pinfunction "PIO5_21") (pintype "bidirectional"))
    )
    (net (code "102") (name "unconnected-(CN2-PadID)") (class "Default")
      (node (ref "CN2") (pin "ID") (pinfunction "ID_ID") (pintype "bidirectional"))
    )
    (net (code "103") (name "unconnected-(H11-MOUNT-PadB2,8)") (class "Default")
      (node (ref "H11") (pin "B2,8") (pinfunction "MOUNT_B2,8") (pintype "passive"))
    )
    (net (code "104") (name "unconnected-(IC2-(ADC5{slash}TMS)PF5-Pad92)") (class "Default")
      (node (ref "IC2") (pin "92") (pinfunction "(ADC5/TMS)PF5_92") (pintype "bidirectional"))
    )
    (net (code "105") (name "unconnected-(IC2-(ADC6{slash}TDO)PF6-Pad91)") (class "Default")
      (node (ref "IC2") (pin "91") (pinfunction "(ADC6/TDO)PF6_91") (pintype "bidirectional"))
    )
    (net (code "106") (name "unconnected-(IC2-(ADC7{slash}TDI)PF7-Pad90)") (class "Default")
      (node (ref "IC2") (pin "90") (pinfunction "(ADC7/TDI)PF7_90") (pintype "bidirectional"))
    )
    (net (code "107") (name "unconnected-(IC2-(ALE)PG2-Pad70)") (class "Default")
      (node (ref "IC2") (pin "70") (pinfunction "(ALE)PG2_70") (pintype "bidirectional"))
    )
    (net (code "108") (name "unconnected-(IC2-(CLKO{slash}ICP3{slash}INT7)PE7-Pad9)") (class "Default")
      (node (ref "IC2") (pin "9") (pinfunction "(CLKO/ICP3/INT7)PE7_9") (pintype "bidirectional"))
    )
    (net (code "109") (name "unconnected-(IC2-(OC0B)PG5-Pad1)") (class "Default")
      (node (ref "IC2") (pin "1") (pinfunction "(OC0B)PG5_1") (pintype "bidirectional"))
    )
    (net (code "110") (name "unconnected-(IC2-(OC1A{slash}PCINT5)PB5-Pad24)") (class "Default")
      (node (ref "IC2") (pin "24") (pinfunction "(OC1A/PCINT5)PB5_24") (pintype "bidirectional"))
    )
    (net (code "111") (name "unconnected-(IC2-(OC1B{slash}PCINT6)PB6-Pad25)") (class "Default")
      (node (ref "IC2") (pin "25") (pinfunction "(OC1B/PCINT6)PB6_25") (pintype "bidirectional"))
    )
    (net (code "112") (name "unconnected-(IC2-(OC2A{slash}PCINT4)PB4-Pad23)") (class "Default")
      (node (ref "IC2") (pin "23") (pinfunction "(OC2A/PCINT4)PB4_23") (pintype "bidirectional"))
    )
    (net (code "113") (name "unconnected-(IC2-(OC3A{slash}AIN1)PE3-Pad5)") (class "Default")
      (node (ref "IC2") (pin "5") (pinfunction "(OC3A/AIN1)PE3_5") (pintype "bidirectional"))
    )
    (net (code "114") (name "unconnected-(IC2-(OC3B{slash}INT4)PE4-Pad6)") (class "Default")
      (node (ref "IC2") (pin "6") (pinfunction "(OC3B/INT4)PE4_6") (pintype "bidirectional"))
    )
    (net (code "115") (name "unconnected-(IC2-(OC3C{slash}INT5)PE5-Pad7)") (class "Default")
      (node (ref "IC2") (pin "7") (pinfunction "(OC3C/INT5)PE5_7") (pintype "bidirectional"))
    )
    (net (code "116") (name "unconnected-(IC2-(RD)PG1-Pad52)") (class "Default")
      (node (ref "IC2") (pin "52") (pinfunction "(RD)PG1_52") (pintype "bidirectional"))
    )
    (net (code "117") (name "unconnected-(IC2-(SCL{slash}INT0)PD0-Pad43)") (class "Default")
      (node (ref "IC2") (pin "43") (pinfunction "(SCL/INT0)PD0_43") (pintype "bidirectional"))
    )
    (net (code "118") (name "unconnected-(IC2-(SDA{slash}INT1)PD1-Pad44)") (class "Default")
      (node (ref "IC2") (pin "44") (pinfunction "(SDA/INT1)PD1_44") (pintype "bidirectional"))
    )
    (net (code "119") (name "unconnected-(IC2-(SS{slash}PCINT0)PB0-Pad19)") (class "Default")
      (node (ref "IC2") (pin "19") (pinfunction "(SS/PCINT0)PB0_19") (pintype "bidirectional"))
    )
    (net (code "120") (name "unconnected-(IC2-(T3{slash}INT6)PE6-Pad8)") (class "Default")
      (node (ref "IC2") (pin "8") (pinfunction "(T3/INT6)PE6_8") (pintype "bidirectional"))
    )
    (net (code "121") (name "unconnected-(IC2-(TOSC1)PG4-Pad29)") (class "Default")
      (node (ref "IC2") (pin "29") (pinfunction "(TOSC1)PG4_29") (pintype "bidirectional"))
    )
    (net (code "122") (name "unconnected-(IC2-(TOSC2)PG3-Pad28)") (class "Default")
      (node (ref "IC2") (pin "28") (pinfunction "(TOSC2)PG3_28") (pintype "bidirectional"))
    )
    (net (code "123") (name "unconnected-(IC2-(WR)PG0-Pad51)") (class "Default")
      (node (ref "IC2") (pin "51") (pinfunction "(WR)PG0_51") (pintype "bidirectional"))
    )
    (net (code "124") (name "unconnected-(IC2-(XCK0{slash}AIN0)PE2-Pad4)") (class "Default")
      (node (ref "IC2") (pin "4") (pinfunction "(XCK0/AIN0)PE2_4") (pintype "bidirectional"))
    )
    (net (code "125") (name "unconnected-(IC2-(XCK1)PD5-Pad48)") (class "Default")
      (node (ref "IC2") (pin "48") (pinfunction "(XCK1)PD5_48") (pintype "bidirectional"))
    )
    (net (code "126") (name "unconnected-(IC2-AREF-Pad98)") (class "Default")
      (node (ref "IC2") (pin "98") (pinfunction "AREF_98") (pintype "bidirectional"))
    )
    (net (code "127") (name "unconnected-(IC2-PH2(XCK2)-Pad14)") (class "Default")
      (node (ref "IC2") (pin "14") (pinfunction "PH2(XCK2)_14") (pintype "bidirectional"))
    )
    (net (code "128") (name "unconnected-(IC2-PH3(OC4A)-Pad15)") (class "Default")
      (node (ref "IC2") (pin "15") (pinfunction "PH3(OC4A)_15") (pintype "bidirectional"))
    )
    (net (code "129") (name "unconnected-(IC2-PH4(OC4B)-Pad16)") (class "Default")
      (node (ref "IC2") (pin "16") (pinfunction "PH4(OC4B)_16") (pintype "bidirectional"))
    )
    (net (code "130") (name "unconnected-(IC2-PH5(OC4C)-Pad17)") (class "Default")
      (node (ref "IC2") (pin "17") (pinfunction "PH5(OC4C)_17") (pintype "bidirectional"))
    )
    (net (code "131") (name "unconnected-(IC2-PH6(OC2B)-Pad18)") (class "Default")
      (node (ref "IC2") (pin "18") (pinfunction "PH6(OC2B)_18") (pintype "bidirectional"))
    )
    (net (code "132") (name "unconnected-(IC2-PH7(T4)-Pad27)") (class "Default")
      (node (ref "IC2") (pin "27") (pinfunction "PH7(T4)_27") (pintype "bidirectional"))
    )
    (net (code "133") (name "unconnected-(IC2-PJ2(XCK3{slash}PCINT11)-Pad65)") (class "Default")
      (node (ref "IC2") (pin "65") (pinfunction "PJ2(XCK3/PCINT11)_65") (pintype "bidirectional"))
    )
    (net (code "134") (name "unconnected-(IC2-PJ3(PCINT12)-Pad66)") (class "Default")
      (node (ref "IC2") (pin "66") (pinfunction "PJ3(PCINT12)_66") (pintype "bidirectional"))
    )
    (net (code "135") (name "unconnected-(IC2-PJ4(PCINT13)-Pad67)") (class "Default")
      (node (ref "IC2") (pin "67") (pinfunction "PJ4(PCINT13)_67") (pintype "bidirectional"))
    )
    (net (code "136") (name "unconnected-(IC2-PJ5(PCINT14)-Pad68)") (class "Default")
      (node (ref "IC2") (pin "68") (pinfunction "PJ5(PCINT14)_68") (pintype "bidirectional"))
    )
    (net (code "137") (name "unconnected-(IC2-PJ6(PCINT15)-Pad69)") (class "Default")
      (node (ref "IC2") (pin "69") (pinfunction "PJ6(PCINT15)_69") (pintype "bidirectional"))
    )
    (net (code "138") (name "unconnected-(IC2-PJ7-Pad79)") (class "Default")
      (node (ref "IC2") (pin "79") (pinfunction "PJ7_79") (pintype "bidirectional"))
    )
    (net (code "139") (name "unconnected-(IC2-PK0(ADC8{slash}PCINT16)-Pad89)") (class "Default")
      (node (ref "IC2") (pin "89") (pinfunction "PK0(ADC8/PCINT16)_89") (pintype "bidirectional"))
    )
    (net (code "140") (name "unconnected-(IC2-PK1(ADC9{slash}PCINT17)-Pad88)") (class "Default")
      (node (ref "IC2") (pin "88") (pinfunction "PK1(ADC9/PCINT17)_88") (pintype "bidirectional"))
    )
    (net (code "141") (name "unconnected-(IC2-PK6(ADC14{slash}PCINT22)-Pad83)") (class "Default")
      (node (ref "IC2") (pin "83") (pinfunction "PK6(ADC14/PCINT22)_83") (pintype "bidirectional"))
    )
    (net (code "142") (name "unconnected-(IC2-PK7(ADC15{slash}PCINT23)-Pad82)") (class "Default")
      (node (ref "IC2") (pin "82") (pinfunction "PK7(ADC15/PCINT23)_82") (pintype "bidirectional"))
    )
    (net (code "143") (name "unconnected-(IC2-PL0(ICP4)-Pad35)") (class "Default")
      (node (ref "IC2") (pin "35") (pinfunction "PL0(ICP4)_35") (pintype "bidirectional"))
    )
    (net (code "144") (name "unconnected-(IC2-PL1(ICP5)-Pad36)") (class "Default")
      (node (ref "IC2") (pin "36") (pinfunction "PL1(ICP5)_36") (pintype "bidirectional"))
    )
    (net (code "145") (name "unconnected-(IC2-PL2(T5)-Pad37)") (class "Default")
      (node (ref "IC2") (pin "37") (pinfunction "PL2(T5)_37") (pintype "bidirectional"))
    )
    (net (code "146") (name "unconnected-(IC2-PL3(OC5A)-Pad38)") (class "Default")
      (node (ref "IC2") (pin "38") (pinfunction "PL3(OC5A)_38") (pintype "bidirectional"))
    )
    (net (code "147") (name "unconnected-(IC2-PL4(OC5B)-Pad39)") (class "Default")
      (node (ref "IC2") (pin "39") (pinfunction "PL4(OC5B)_39") (pintype "bidirectional"))
    )
    (net (code "148") (name "unconnected-(IC2-PL5(OC5C)-Pad40)") (class "Default")
      (node (ref "IC2") (pin "40") (pinfunction "PL5(OC5C)_40") (pintype "bidirectional"))
    )
    (net (code "149") (name "unconnected-(IC2-PL6-Pad41)") (class "Default")
      (node (ref "IC2") (pin "41") (pinfunction "PL6_41") (pintype "bidirectional"))
    )
    (net (code "150") (name "unconnected-(IC2-PL7-Pad42)") (class "Default")
      (node (ref "IC2") (pin "42") (pinfunction "PL7_42") (pintype "bidirectional"))
    )
    (net (code "151") (name "unconnected-(IC3-CBUS2-Pad13)") (class "Default")
      (node (ref "IC3") (pin "13") (pinfunction "CBUS2_13") (pintype "input"))
    )
    (net (code "152") (name "unconnected-(IC3-CBUS3-Pad14)") (class "Default")
      (node (ref "IC3") (pin "14") (pinfunction "CBUS3_14") (pintype "input"))
    )
    (net (code "153") (name "unconnected-(IC3-CBUS4-Pad12)") (class "Default")
      (node (ref "IC3") (pin "12") (pinfunction "CBUS4_12") (pintype "input"))
    )
    (net (code "154") (name "unconnected-(IC3-OSCI-Pad27)") (class "Default")
      (node (ref "IC3") (pin "27") (pinfunction "OSCI_27") (pintype "input"))
    )
    (net (code "155") (name "unconnected-(IC3-OSCO-Pad28)") (class "Default")
      (node (ref "IC3") (pin "28") (pinfunction "OSCO_28") (pintype "input"))
    )
    (net (code "156") (name "unconnected-(IC3-~{CTS}-Pad11)") (class "Default")
      (node (ref "IC3") (pin "11") (pinfunction "~{CTS}_11") (pintype "input"))
    )
    (net (code "157") (name "unconnected-(IC3-~{DCD}-Pad10)") (class "Default")
      (node (ref "IC3") (pin "10") (pinfunction "~{DCD}_10") (pintype "input"))
    )
    (net (code "158") (name "unconnected-(IC3-~{DSR}-Pad9)") (class "Default")
      (node (ref "IC3") (pin "9") (pinfunction "~{DSR}_9") (pintype "input"))
    )
    (net (code "159") (name "unconnected-(IC3-~{DTR}-Pad2)") (class "Default")
      (node (ref "IC3") (pin "2") (pinfunction "~{DTR}_2") (pintype "input"))
    )
    (net (code "160") (name "unconnected-(IC3-~{RESET}-Pad19)") (class "Default")
      (node (ref "IC3") (pin "19") (pinfunction "~{RESET}_19") (pintype "input"))
    )
    (net (code "161") (name "unconnected-(IC3-~{RI}-Pad6)") (class "Default")
      (node (ref "IC3") (pin "6") (pinfunction "~{RI}_6") (pintype "input"))
    )
    (net (code "162") (name "unconnected-(IC3-~{RTS}-Pad3)") (class "Default")
      (node (ref "IC3") (pin "3") (pinfunction "~{RTS}_3") (pintype "input"))
    )
    (net (code "163") (name "unconnected-(U9-CP1-Pad13)") (class "Default")
      (node (ref "U9") (pin "13") (pinfunction "CP1_13") (pintype "bidirectional"))
    )
    (net (code "164") (name "unconnected-(U9-CP2-Pad15)") (class "Default")
      (node (ref "U9") (pin "15") (pinfunction "CP2_15") (pintype "bidirectional"))
    )
    (net (code "165") (name "unconnected-(U9-CP3-Pad17)") (class "Default")
      (node (ref "U9") (pin "17") (pinfunction "CP3_17") (pintype "bidirectional"))
    )
    (net (code "166") (name "unconnected-(U9-CP4-Pad19)") (class "Default")
      (node (ref "U9") (pin "19") (pinfunction "CP4_19") (pintype "bidirectional"))
    )
    (net (code "167") (name "unconnected-(U9-CP5-Pad29)") (class "Default")
      (node (ref "U9") (pin "29") (pinfunction "CP5_29") (pintype "bidirectional"))
    )
    (net (code "168") (name "unconnected-(U9-CP6-Pad31)") (class "Default")
      (node (ref "U9") (pin "31") (pinfunction "CP6_31") (pintype "bidirectional"))
    )
    (net (code "169") (name "unconnected-(U9-CP7-Pad33)") (class "Default")
      (node (ref "U9") (pin "33") (pinfunction "CP7_33") (pintype "bidirectional"))
    )
    (net (code "170") (name "unconnected-(U9-CP8-Pad35)") (class "Default")
      (node (ref "U9") (pin "35") (pinfunction "CP8_35") (pintype "bidirectional"))
    )
    (net (code "171") (name "unconnected-(U9-CTS1-Pad11)") (class "Default")
      (node (ref "U9") (pin "11") (pinfunction "CTS1_11") (pintype "bidirectional"))
    )
    (net (code "172") (name "unconnected-(U9-CTS2-Pad27)") (class "Default")
      (node (ref "U9") (pin "27") (pinfunction "CTS2_27") (pintype "bidirectional"))
    )
    (net (code "173") (name "unconnected-(U9-RTS1-Pad7)") (class "Default")
      (node (ref "U9") (pin "7") (pinfunction "RTS1_7") (pintype "bidirectional"))
    )
    (net (code "174") (name "unconnected-(U9-RTS2-Pad23)") (class "Default")
      (node (ref "U9") (pin "23") (pinfunction "RTS2_23") (pintype "bidirectional"))
    )
    (net (code "175") (name "unconnected-(U9-~{RESET}-Pad1)") (class "Default")
      (node (ref "U9") (pin "1") (pinfunction "~{RESET}_1") (pintype "bidirectional"))
    )
    (net (code "176") (name "unconnected-(U10-AIO1-Pad35)") (class "Default")
      (node (ref "U10") (pin "35") (pinfunction "AIO1_35") (pintype "bidirectional"))
    )
    (net (code "177") (name "unconnected-(U10-AIO2-Pad30)") (class "Default")
      (node (ref "U10") (pin "30") (pinfunction "AIO2_30") (pintype "bidirectional"))
    )
    (net (code "178") (name "unconnected-(U10-NC-Pad26)") (class "Default")
      (node (ref "U10") (pin "26") (pinfunction "NC_26") (pintype "bidirectional"))
    )
    (net (code "179") (name "unconnected-(U10-PCMCLK-Pad7)") (class "Default")
      (node (ref "U10") (pin "7") (pinfunction "PCMCLK_7") (pintype "bidirectional"))
    )
    (net (code "180") (name "unconnected-(U10-PCMIN-Pad9)") (class "Default")
      (node (ref "U10") (pin "9") (pinfunction "PCMIN_9") (pintype "bidirectional"))
    )
    (net (code "181") (name "unconnected-(U10-PCMOUT-Pad10)") (class "Default")
      (node (ref "U10") (pin "10") (pinfunction "PCMOUT_10") (pintype "bidirectional"))
    )
    (net (code "182") (name "unconnected-(U10-PCMSYNC-Pad8)") (class "Default")
      (node (ref "U10") (pin "8") (pinfunction "PCMSYNC_8") (pintype "bidirectional"))
    )
    (net (code "183") (name "unconnected-(U10-PIO3-Pad20)") (class "Default")
      (node (ref "U10") (pin "20") (pinfunction "PIO3_20") (pintype "bidirectional"))
    )
    (net (code "184") (name "unconnected-(U10-PIO6-Pad3)") (class "Default")
      (node (ref "U10") (pin "3") (pinfunction "PIO6_3") (pintype "bidirectional"))
    )
    (net (code "185") (name "unconnected-(U10-PIO7-Pad4)") (class "Default")
      (node (ref "U10") (pin "4") (pinfunction "PIO7_4") (pintype "bidirectional"))
    )
    (net (code "186") (name "unconnected-(U10-PIO8-Pad34)") (class "Default")
      (node (ref "U10") (pin "34") (pinfunction "PIO8_34") (pintype "bidirectional"))
    )
    (net (code "187") (name "unconnected-(U10-PIO9-Pad33)") (class "Default")
      (node (ref "U10") (pin "33") (pinfunction "PIO9_33") (pintype "bidirectional"))
    )
    (net (code "188") (name "unconnected-(U10-PIO10-Pad32)") (class "Default")
      (node (ref "U10") (pin "32") (pinfunction "PIO10_32") (pintype "bidirectional"))
    )
    (net (code "189") (name "unconnected-(U10-PIO11-Pad31)") (class "Default")
      (node (ref "U10") (pin "31") (pinfunction "PIO11_31") (pintype "bidirectional"))
    )
    (net (code "190") (name "unconnected-(U10-RESET-Pad5)") (class "Default")
      (node (ref "U10") (pin "5") (pinfunction "RESET_5") (pintype "bidirectional"))
    )
    (net (code "191") (name "unconnected-(U10-SPICLK-Pad6)") (class "Default")
      (node (ref "U10") (pin "6") (pinfunction "SPICLK_6") (pintype "bidirectional"))
    )
    (net (code "192") (name "unconnected-(U10-SPICSB-Pad23)") (class "Default")
      (node (ref "U10") (pin "23") (pinfunction "SPICSB_23") (pintype "bidirectional"))
    )
    (net (code "193") (name "unconnected-(U10-SPIMISO-Pad24)") (class "Default")
      (node (ref "U10") (pin "24") (pinfunction "SPIMISO_24") (pintype "bidirectional"))
    )
    (net (code "194") (name "unconnected-(U10-SPIMOSI-Pad2)") (class "Default")
      (node (ref "U10") (pin "2") (pinfunction "SPIMOSI_2") (pintype "bidirectional"))
    )
    (net (code "195") (name "unconnected-(U10-USBD+-Pad17)") (class "Default")
      (node (ref "U10") (pin "17") (pinfunction "USBD+_17") (pintype "bidirectional"))
    )
    (net (code "196") (name "unconnected-(U10-USBD--Pad18)") (class "Default")
      (node (ref "U10") (pin "18") (pinfunction "USBD-_18") (pintype "bidirectional"))
    )
    (net (code "197") (name "unconnected-(U47-CH-Pad11)") (class "Default")
      (node (ref "U47") (pin "11") (pinfunction "CH_11") (pintype "bidirectional"))
    )
  )
)
